# old_line_kick.net
KiCad netlist of a schematic drawn in EAGLE
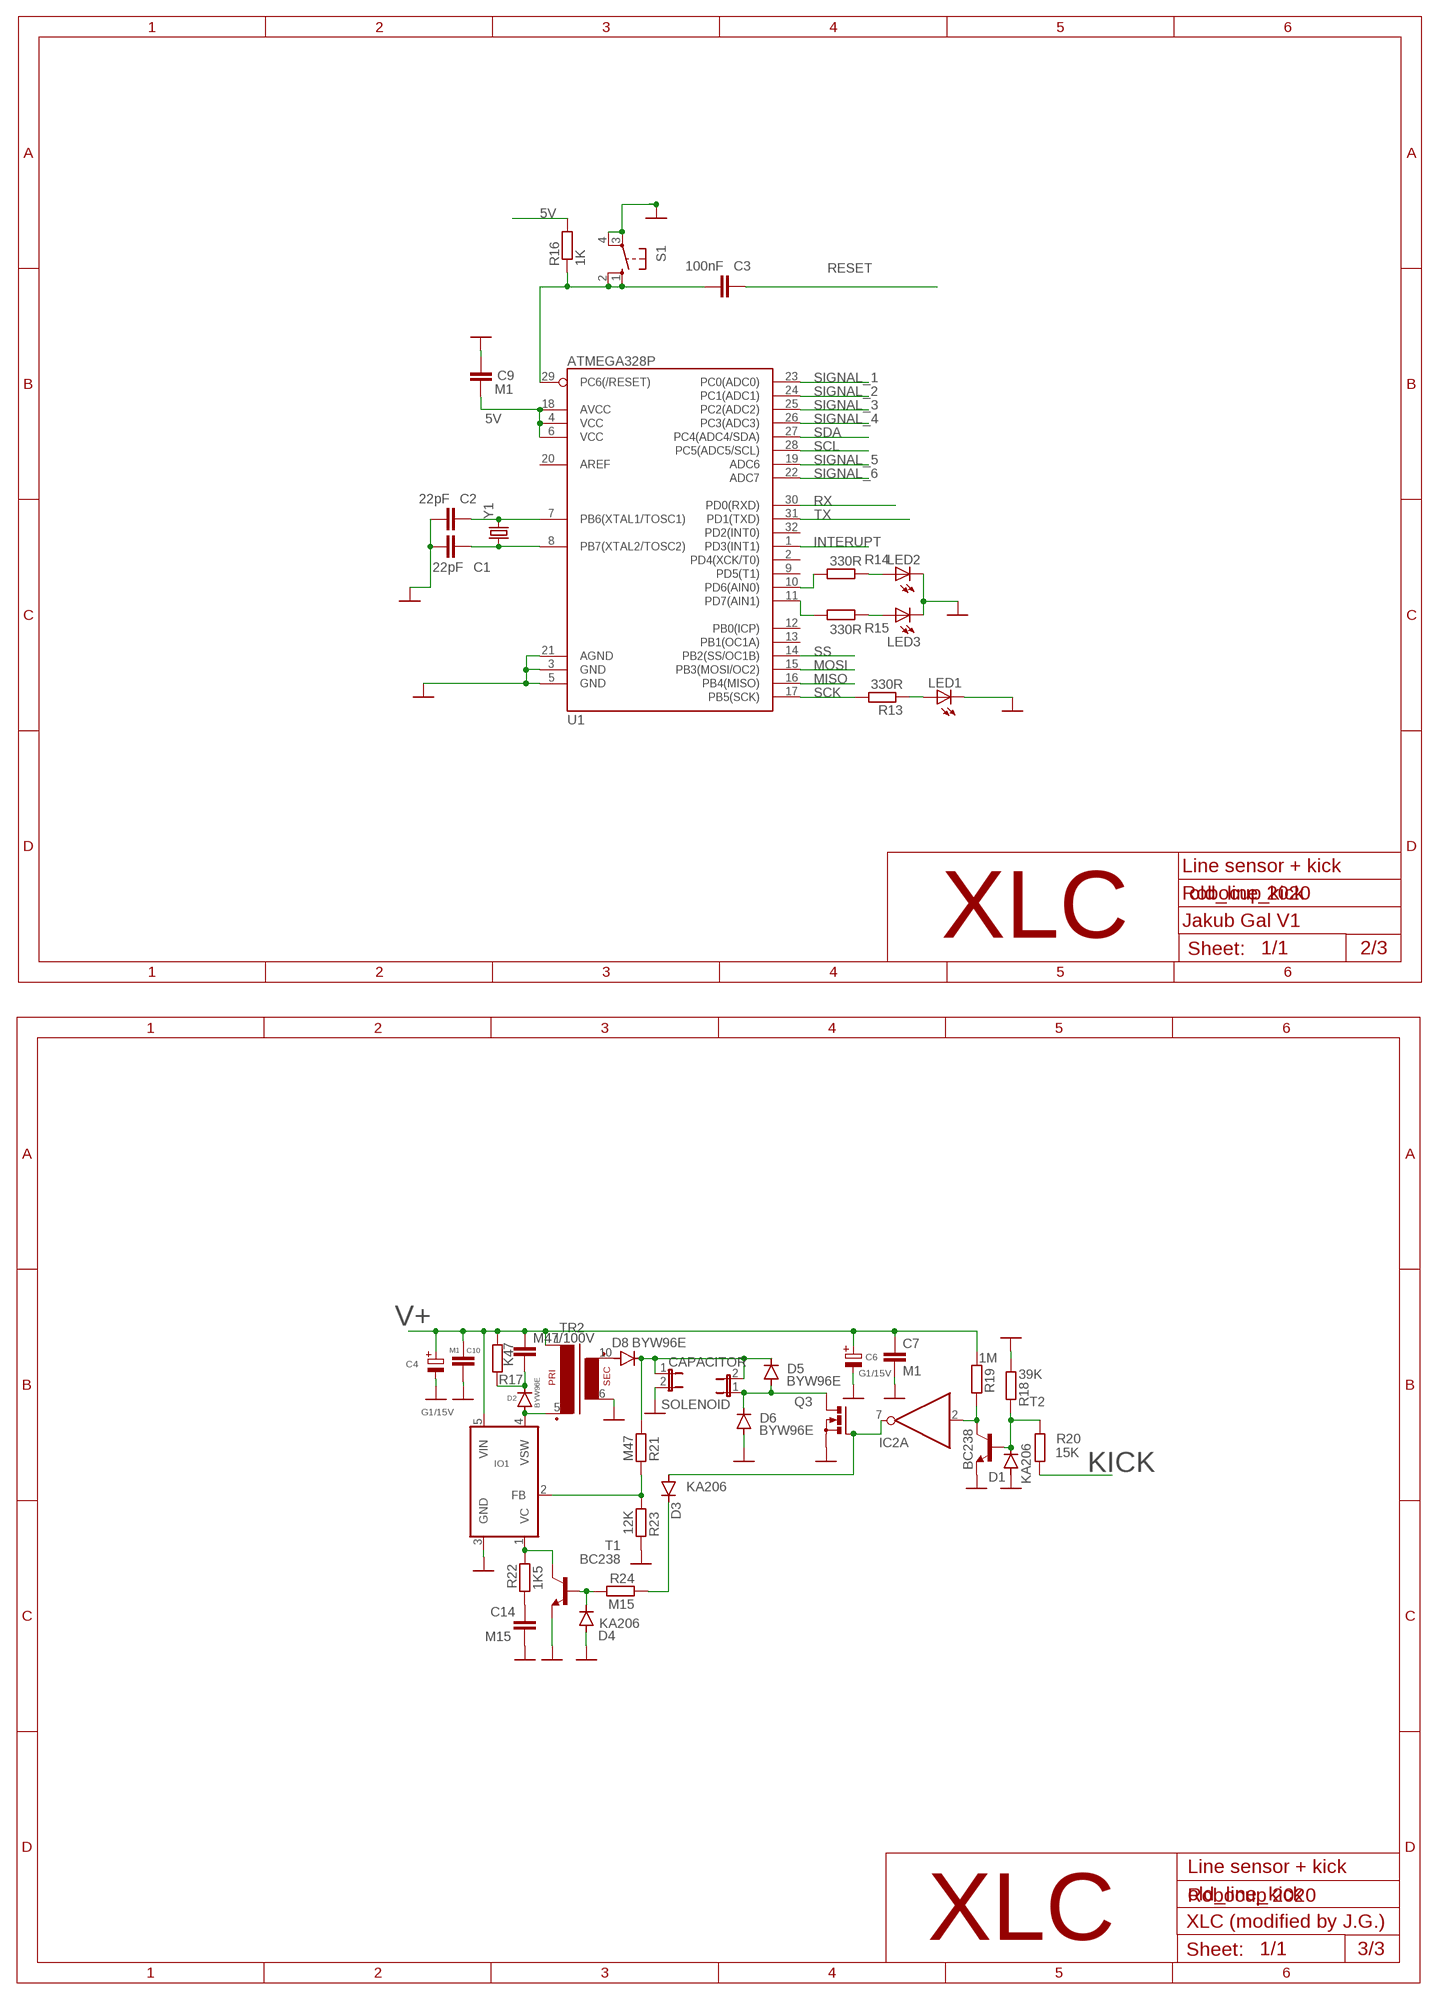
[diagram p0: schematic, sheet 1, part 1 of 2]
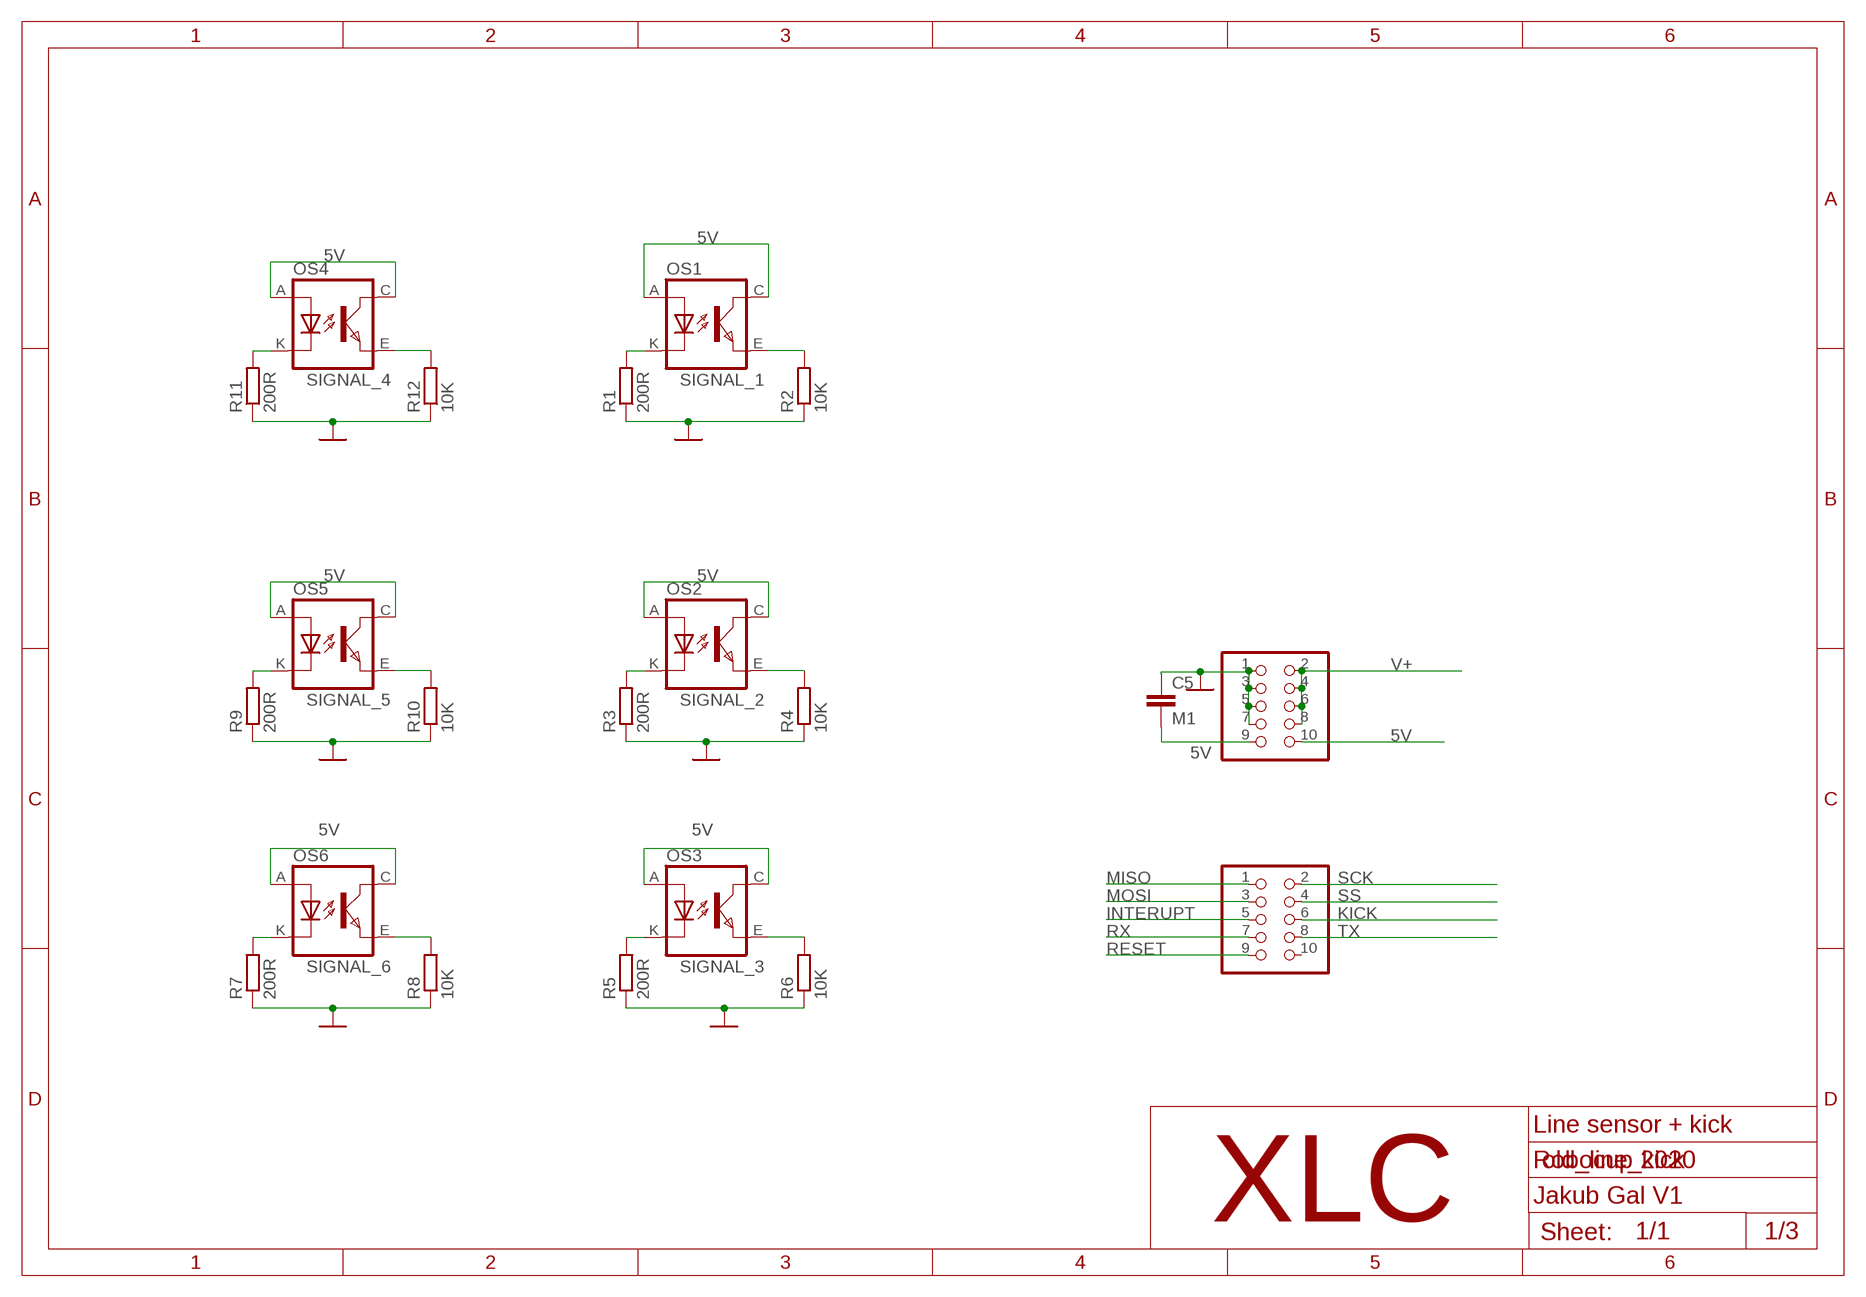
[diagram p1: schematic, sheet 1, part 2 of 2]

(export (version "E")
  (design (tool "Eeschema 10.0.6"))
  (components
    (comp (ref "C1")
      (value "22pF")
      (footprint "eagle-import:C0603")
      (libsource (lib "eagle-import") (part "rcl@1_C-EUC0603"))
    )
    (comp (ref "C2")
      (value "22pF")
      (footprint "eagle-import:C0603")
      (libsource (lib "eagle-import") (part "rcl@1_C-EUC0603"))
    )
    (comp (ref "C3")
      (value "100nF")
      (footprint "eagle-import:C0603")
      (libsource (lib "eagle-import") (part "rcl@1_C-EUC0603"))
    )
    (comp (ref "C4")
      (value "G1/15V")
      (footprint "eagle-import:E-2,5_7-RAD")
      (libsource (lib "eagle-import") (part "KOND-ELEKT-2,5/7"))
    )
    (comp (ref "C5")
      (value "M1")
      (footprint "eagle-import:C0603")
      (libsource (lib "eagle-import") (part "C-EUC0603"))
    )
    (comp (ref "C6")
      (value "G1/15V")
      (footprint "eagle-import:E-2,5_7-RAD")
      (libsource (lib "eagle-import") (part "KOND-ELEKT-2,5/7"))
    )
    (comp (ref "C7")
      (value "M1")
      (footprint "eagle-import:C0805K")
      (libsource (lib "eagle-import") (part "resistor_C-EUC0805K"))
    )
    (comp (ref "C9")
      (value "M1")
      (footprint "eagle-import:C0603")
      (libsource (lib "eagle-import") (part "rcl@1_C-EUC0603"))
    )
    (comp (ref "C10")
      (value "M1")
      (footprint "eagle-import:C0805K")
      (libsource (lib "eagle-import") (part "resistor_C-EUC0805K"))
    )
    (comp (ref "C14")
      (value "M15")
      (footprint "eagle-import:C0805K")
      (libsource (lib "eagle-import") (part "resistor_C-EUC0805K"))
    )
    (comp (ref "CAPACITOR")
      (value "JP1E")
      (footprint "eagle-import:JP1")
      (libsource (lib "eagle-import") (part "JP1E"))
    )
    (comp (ref "D1")
      (value "KA206")
      (footprint "eagle-import:D-7.5")
      (libsource (lib "eagle-import") (part "DIODE-D-7.5"))
    )
    (comp (ref "D2")
      (value "BYW96E")
      (footprint "eagle-import:SOD64-10")
      (libsource (lib "eagle-import") (part "BYW96"))
    )
    (comp (ref "D3")
      (value "KA206")
      (footprint "eagle-import:D-7.5")
      (libsource (lib "eagle-import") (part "DIODE-D-7.5"))
    )
    (comp (ref "D4")
      (value "KA206")
      (footprint "eagle-import:D-7.5")
      (libsource (lib "eagle-import") (part "DIODE-D-7.5"))
    )
    (comp (ref "D5")
      (value "BYW96E")
      (footprint "eagle-import:SOD64-10")
      (libsource (lib "eagle-import") (part "BYW96"))
    )
    (comp (ref "D6")
      (value "BYW96E")
      (footprint "eagle-import:SOD64-10")
      (libsource (lib "eagle-import") (part "BYW96"))
    )
    (comp (ref "D8")
      (value "BYW96E")
      (footprint "eagle-import:SOD64-10")
      (libsource (lib "eagle-import") (part "BYW96"))
    )
    (comp (ref "IC2")
      (value "MIC4423BM")
      (footprint "eagle-import:SO08")
      (libsource (lib "eagle-import") (part "MIC4423BM"))
    )
    (comp (ref "IO1")
      (value "LT1071V")
      (footprint "eagle-import:TO220-5P")
      (libsource (lib "eagle-import") (part "LT1071V"))
    )
    (comp (ref "JP2")
      (value "PINHD-2X5")
      (footprint "eagle-import:2X05")
      (libsource (lib "eagle-import") (part "PINHD-2X5"))
    )
    (comp (ref "JP3")
      (value "PINHD-2X5")
      (footprint "eagle-import:2X05")
      (libsource (lib "eagle-import") (part "PINHD-2X5"))
    )
    (comp (ref "LED1")
      (value "LEDCHIPLED_0603")
      (footprint "eagle-import:CHIPLED_0603")
      (libsource (lib "eagle-import") (part "LEDCHIPLED_0603"))
    )
    (comp (ref "LED2")
      (value "LEDCHIPLED_0603")
      (footprint "eagle-import:CHIPLED_0603")
      (libsource (lib "eagle-import") (part "LEDCHIPLED_0603"))
    )
    (comp (ref "LED3")
      (value "LEDCHIPLED_0603")
      (footprint "eagle-import:CHIPLED_0603")
      (libsource (lib "eagle-import") (part "LEDCHIPLED_0603"))
    )
    (comp (ref "M47/100V")
      (value "C-EUC0805K")
      (footprint "eagle-import:C0805K")
      (libsource (lib "eagle-import") (part "resistor_C-EUC0805K"))
    )
    (comp (ref "OS1")
      (value "TCRT5000")
      (footprint "eagle-import:TCRT5000")
      (libsource (lib "eagle-import") (part "TCRT5000"))
    )
    (comp (ref "OS2")
      (value "TCRT5000")
      (footprint "eagle-import:TCRT5000")
      (libsource (lib "eagle-import") (part "TCRT5000"))
    )
    (comp (ref "OS3")
      (value "TCRT5000")
      (footprint "eagle-import:TCRT5000")
      (libsource (lib "eagle-import") (part "TCRT5000"))
    )
    (comp (ref "OS4")
      (value "TCRT5000")
      (footprint "eagle-import:TCRT5000")
      (fields (field (name "SPICEPREFIX") "O"))
      (libsource (lib "eagle-import") (part "TCRT5000"))
    )
    (comp (ref "OS5")
      (value "TCRT5000")
      (footprint "eagle-import:TCRT5000")
      (libsource (lib "eagle-import") (part "TCRT5000"))
    )
    (comp (ref "OS6")
      (value "TCRT5000")
      (footprint "eagle-import:TCRT5000")
      (fields (field (name "SPICEPREFIX") "O"))
      (libsource (lib "eagle-import") (part "TCRT5000"))
    )
    (comp (ref "Q3")
      (value "PMOSFET_NTO220BV")
      (footprint "eagle-import:TO220BV")
      (libsource (lib "eagle-import") (part "PMOSFET_NTO220BV"))
    )
    (comp (ref "R1")
      (value "200R")
      (footprint "eagle-import:R0603")
      (libsource (lib "eagle-import") (part "R-EU_R0603"))
    )
    (comp (ref "R2")
      (value "10K")
      (footprint "eagle-import:R0603")
      (libsource (lib "eagle-import") (part "R-EU_R0603"))
    )
    (comp (ref "R3")
      (value "200R")
      (footprint "eagle-import:R0603")
      (libsource (lib "eagle-import") (part "R-EU_R0603"))
    )
    (comp (ref "R4")
      (value "10K")
      (footprint "eagle-import:R0603")
      (libsource (lib "eagle-import") (part "R-EU_R0603"))
    )
    (comp (ref "R5")
      (value "200R")
      (footprint "eagle-import:R0603")
      (libsource (lib "eagle-import") (part "R-EU_R0603"))
    )
    (comp (ref "R6")
      (value "10K")
      (footprint "eagle-import:R0603")
      (libsource (lib "eagle-import") (part "R-EU_R0603"))
    )
    (comp (ref "R7")
      (value "200R")
      (footprint "eagle-import:R0603")
      (libsource (lib "eagle-import") (part "R-EU_R0603"))
    )
    (comp (ref "R8")
      (value "10K")
      (footprint "eagle-import:R0603")
      (libsource (lib "eagle-import") (part "R-EU_R0603"))
    )
    (comp (ref "R9")
      (value "200R")
      (footprint "eagle-import:R0603")
      (libsource (lib "eagle-import") (part "R-EU_R0603"))
    )
    (comp (ref "R10")
      (value "10K")
      (footprint "eagle-import:R0603")
      (libsource (lib "eagle-import") (part "R-EU_R0603"))
    )
    (comp (ref "R11")
      (value "200R")
      (footprint "eagle-import:R0603")
      (libsource (lib "eagle-import") (part "R-EU_R0603"))
    )
    (comp (ref "R12")
      (value "10K")
      (footprint "eagle-import:R0603")
      (libsource (lib "eagle-import") (part "R-EU_R0603"))
    )
    (comp (ref "R13")
      (value "330R")
      (footprint "eagle-import:R0603")
      (libsource (lib "eagle-import") (part "R-EU_R0603"))
    )
    (comp (ref "R14")
      (value "330R")
      (footprint "eagle-import:R0603")
      (libsource (lib "eagle-import") (part "R-EU_R0603"))
    )
    (comp (ref "R15")
      (value "330R")
      (footprint "eagle-import:R0603")
      (libsource (lib "eagle-import") (part "R-EU_R0603"))
    )
    (comp (ref "R16")
      (value "1K")
      (footprint "eagle-import:R0603")
      (libsource (lib "eagle-import") (part "R-EU_R0603"))
    )
    (comp (ref "R17")
      (value "K47")
      (footprint "eagle-import:R0603")
      (libsource (lib "eagle-import") (part "resistor_R-EU_R0603"))
    )
    (comp (ref "R18")
      (value "39K")
      (footprint "eagle-import:R0603")
      (libsource (lib "eagle-import") (part "resistor_R-EU_R0603"))
    )
    (comp (ref "R19")
      (value "1M")
      (footprint "eagle-import:R0603")
      (libsource (lib "eagle-import") (part "resistor_R-EU_R0603"))
    )
    (comp (ref "R20")
      (value "15K")
      (footprint "eagle-import:R0603")
      (libsource (lib "eagle-import") (part "resistor_R-EU_R0603"))
    )
    (comp (ref "R21")
      (value "M47")
      (footprint "eagle-import:R0603")
      (libsource (lib "eagle-import") (part "resistor_R-EU_R0603"))
    )
    (comp (ref "R22")
      (value "1K5")
      (footprint "eagle-import:R0603")
      (libsource (lib "eagle-import") (part "resistor_R-EU_R0603"))
    )
    (comp (ref "R23")
      (value "12K")
      (footprint "eagle-import:R0603")
      (libsource (lib "eagle-import") (part "resistor_R-EU_R0603"))
    )
    (comp (ref "R24")
      (value "M15")
      (footprint "eagle-import:R0603")
      (libsource (lib "eagle-import") (part "resistor_R-EU_R0603"))
    )
    (comp (ref "S1")
      (value "10-XX")
      (footprint "eagle-import:B3F-10XX")
      (fields (field (name "MPN") "B3F-1000"))
      (libsource (lib "eagle-import") (part "10-XX"))
    )
    (comp (ref "SOLENOID")
      (value "JP1E")
      (footprint "eagle-import:JP1")
      (libsource (lib "eagle-import") (part "JP1E"))
    )
    (comp (ref "T1")
      (value "BC238")
      (footprint "eagle-import:TO92")
      (libsource (lib "eagle-import") (part "BC238"))
    )
    (comp (ref "T2")
      (value "BC238")
      (footprint "eagle-import:TO92")
      (libsource (lib "eagle-import") (part "BC238"))
    )
    (comp (ref "TR2")
      (value "TRAFO-E10-R\"\"")
      (footprint "eagle-import:TRAFO-EE17X20")
      (libsource (lib "eagle-import") (part "TRAFO-E10-R{dblquote}{dblquote}"))
    )
    (comp (ref "U1")
      (value "ATMEGA328P")
      (footprint "eagle-import:TQFP32-08")
      (libsource (lib "eagle-import") (part "ATMEGA328_SMT"))
    )
    (comp (ref "Y1")
      (value "CRYSTALHC49US")
      (footprint "eagle-import:HC49US")
      (libsource (lib "eagle-import") (part "CRYSTALHC49US"))
    )
  )
  (nets
    (net (code "1") (name "/5V") (class "Default")
      (node (ref "C5") (pin "2") (pinfunction "2_2") (pintype "passive"))
      (node (ref "C9") (pin "1") (pinfunction "1_1") (pintype "passive"))
      (node (ref "JP3") (pin "10") (pinfunction "10_10") (pintype "passive"))
      (node (ref "JP3") (pin "9") (pinfunction "9_9") (pintype "passive"))
      (node (ref "OS1") (pin "A") (pinfunction "ANODE_A") (pintype "passive"))
      (node (ref "OS1") (pin "C") (pinfunction "COLLECTOR_C") (pintype "passive"))
      (node (ref "OS2") (pin "A") (pinfunction "ANODE_A") (pintype "passive"))
      (node (ref "OS2") (pin "C") (pinfunction "COLLECTOR_C") (pintype "passive"))
      (node (ref "OS3") (pin "A") (pinfunction "ANODE_A") (pintype "passive"))
      (node (ref "OS3") (pin "C") (pinfunction "COLLECTOR_C") (pintype "passive"))
      (node (ref "OS4") (pin "A") (pinfunction "ANODE_A") (pintype "passive"))
      (node (ref "OS4") (pin "C") (pinfunction "COLLECTOR_C") (pintype "passive"))
      (node (ref "OS5") (pin "A") (pinfunction "ANODE_A") (pintype "passive"))
      (node (ref "OS5") (pin "C") (pinfunction "COLLECTOR_C") (pintype "passive"))
      (node (ref "OS6") (pin "A") (pinfunction "ANODE_A") (pintype "passive"))
      (node (ref "OS6") (pin "C") (pinfunction "COLLECTOR_C") (pintype "passive"))
      (node (ref "R16") (pin "2") (pinfunction "2_2") (pintype "passive"))
      (node (ref "U1") (pin "18") (pinfunction "AVCC_18") (pintype "bidirectional"))
      (node (ref "U1") (pin "4") (pinfunction "VCC_4") (pintype "bidirectional"))
      (node (ref "U1") (pin "6") (pinfunction "VCC_6") (pintype "bidirectional"))
    )
    (net (code "2") (name "/INTERUPT") (class "Default")
      (node (ref "JP2") (pin "5") (pinfunction "5_5") (pintype "passive"))
      (node (ref "U1") (pin "1") (pinfunction "PD3(INT1)_1") (pintype "bidirectional"))
    )
    (net (code "3") (name "/KICK") (class "Default")
      (node (ref "JP2") (pin "6") (pinfunction "6_6") (pintype "passive"))
      (node (ref "R20") (pin "1") (pinfunction "1_1") (pintype "passive"))
    )
    (net (code "4") (name "/MISO") (class "Default")
      (node (ref "JP2") (pin "1") (pinfunction "1_1") (pintype "passive"))
      (node (ref "U1") (pin "16") (pinfunction "PB4(MISO)_16") (pintype "bidirectional"))
    )
    (net (code "5") (name "/MOSI") (class "Default")
      (node (ref "JP2") (pin "3") (pinfunction "3_3") (pintype "passive"))
      (node (ref "U1") (pin "15") (pinfunction "PB3(MOSI/OC2)_15") (pintype "bidirectional"))
    )
    (net (code "6") (name "/RESET") (class "Default")
      (node (ref "C3") (pin "2") (pinfunction "2_2") (pintype "passive"))
      (node (ref "JP2") (pin "9") (pinfunction "9_9") (pintype "passive"))
    )
    (net (code "7") (name "/RX") (class "Default")
      (node (ref "JP2") (pin "7") (pinfunction "7_7") (pintype "passive"))
      (node (ref "U1") (pin "30") (pinfunction "PD0(RXD)_30") (pintype "bidirectional"))
    )
    (net (code "8") (name "/SCK") (class "Default")
      (node (ref "JP2") (pin "2") (pinfunction "2_2") (pintype "passive"))
      (node (ref "R13") (pin "2") (pinfunction "2_2") (pintype "passive"))
      (node (ref "U1") (pin "17") (pinfunction "PB5(SCK)_17") (pintype "bidirectional"))
    )
    (net (code "9") (name "/SCL") (class "Default")
      (node (ref "U1") (pin "28") (pinfunction "PC5(ADC5/SCL)_28") (pintype "bidirectional"))
    )
    (net (code "10") (name "/SDA") (class "Default")
      (node (ref "U1") (pin "27") (pinfunction "PC4(ADC4/SDA)_27") (pintype "bidirectional"))
    )
    (net (code "11") (name "/SIGNAL_1") (class "Default")
      (node (ref "OS1") (pin "E") (pinfunction "EMITTER_E") (pintype "passive"))
      (node (ref "R2") (pin "2") (pinfunction "2_2") (pintype "passive"))
      (node (ref "U1") (pin "23") (pinfunction "PC0(ADC0)_23") (pintype "bidirectional"))
    )
    (net (code "12") (name "/SIGNAL_2") (class "Default")
      (node (ref "OS2") (pin "E") (pinfunction "EMITTER_E") (pintype "passive"))
      (node (ref "R4") (pin "2") (pinfunction "2_2") (pintype "passive"))
      (node (ref "U1") (pin "24") (pinfunction "PC1(ADC1)_24") (pintype "bidirectional"))
    )
    (net (code "13") (name "/SIGNAL_3") (class "Default")
      (node (ref "OS3") (pin "E") (pinfunction "EMITTER_E") (pintype "passive"))
      (node (ref "R6") (pin "2") (pinfunction "2_2") (pintype "passive"))
      (node (ref "U1") (pin "25") (pinfunction "PC2(ADC2)_25") (pintype "bidirectional"))
    )
    (net (code "14") (name "/SIGNAL_4") (class "Default")
      (node (ref "OS4") (pin "E") (pinfunction "EMITTER_E") (pintype "passive"))
      (node (ref "R12") (pin "2") (pinfunction "2_2") (pintype "passive"))
      (node (ref "U1") (pin "26") (pinfunction "PC3(ADC3)_26") (pintype "bidirectional"))
    )
    (net (code "15") (name "/SIGNAL_5") (class "Default")
      (node (ref "OS5") (pin "E") (pinfunction "EMITTER_E") (pintype "passive"))
      (node (ref "R10") (pin "2") (pinfunction "2_2") (pintype "passive"))
      (node (ref "U1") (pin "19") (pinfunction "ADC6_19") (pintype "bidirectional"))
    )
    (net (code "16") (name "/SIGNAL_6") (class "Default")
      (node (ref "OS6") (pin "E") (pinfunction "EMITTER_E") (pintype "passive"))
      (node (ref "R8") (pin "2") (pinfunction "2_2") (pintype "passive"))
      (node (ref "U1") (pin "22") (pinfunction "ADC7_22") (pintype "bidirectional"))
    )
    (net (code "17") (name "/SS") (class "Default")
      (node (ref "JP2") (pin "4") (pinfunction "4_4") (pintype "passive"))
      (node (ref "U1") (pin "14") (pinfunction "PB2(SS/OC1B)_14") (pintype "bidirectional"))
    )
    (net (code "18") (name "/TX") (class "Default")
      (node (ref "JP2") (pin "8") (pinfunction "8_8") (pintype "passive"))
      (node (ref "U1") (pin "31") (pinfunction "PD1(TXD)_31") (pintype "bidirectional"))
    )
    (net (code "19") (name "/V+") (class "Default")
      (node (ref "C10") (pin "1") (pinfunction "1_1") (pintype "passive"))
      (node (ref "C4") (pin "+") (pinfunction "+_+") (pintype "passive"))
      (node (ref "C6") (pin "+") (pinfunction "+_+") (pintype "passive"))
      (node (ref "C7") (pin "1") (pinfunction "1_1") (pintype "passive"))
      (node (ref "IO1") (pin "5") (pinfunction "VIN_5") (pintype "power_in"))
      (node (ref "JP3") (pin "2") (pinfunction "2_2") (pintype "passive"))
      (node (ref "JP3") (pin "4") (pinfunction "4_4") (pintype "passive"))
      (node (ref "JP3") (pin "6") (pinfunction "6_6") (pintype "passive"))
      (node (ref "JP3") (pin "8") (pinfunction "8_8") (pintype "passive"))
      (node (ref "M47/100V") (pin "1") (pinfunction "1_1") (pintype "passive"))
      (node (ref "R17") (pin "1") (pinfunction "1_1") (pintype "passive"))
      (node (ref "R19") (pin "2") (pinfunction "2_2") (pintype "passive"))
      (node (ref "TR2") (pin "1") (pinfunction "1_1") (pintype "passive"))
    )
    (net (code "20") (name "GND") (class "Default")
      (node (ref "C1") (pin "1") (pinfunction "1_1") (pintype "passive"))
      (node (ref "C10") (pin "2") (pinfunction "2_2") (pintype "passive"))
      (node (ref "C14") (pin "2") (pinfunction "2_2") (pintype "passive"))
      (node (ref "C2") (pin "1") (pinfunction "1_1") (pintype "passive"))
      (node (ref "C4") (pin "-") (pinfunction "-_-") (pintype "passive"))
      (node (ref "C5") (pin "1") (pinfunction "1_1") (pintype "passive"))
      (node (ref "C6") (pin "-") (pinfunction "-_-") (pintype "passive"))
      (node (ref "C7") (pin "2") (pinfunction "2_2") (pintype "passive"))
      (node (ref "C9") (pin "2") (pinfunction "2_2") (pintype "passive"))
      (node (ref "CAPACITOR") (pin "2") (pinfunction "2_2") (pintype "passive"))
      (node (ref "D1") (pin "A") (pinfunction "A_A") (pintype "passive"))
      (node (ref "D4") (pin "A") (pinfunction "A_A") (pintype "passive"))
      (node (ref "D6") (pin "A") (pinfunction "A_A") (pintype "passive"))
      (node (ref "IO1") (pin "3") (pinfunction "GND_3") (pintype "power_in"))
      (node (ref "JP3") (pin "1") (pinfunction "1_1") (pintype "passive"))
      (node (ref "JP3") (pin "3") (pinfunction "3_3") (pintype "passive"))
      (node (ref "JP3") (pin "5") (pinfunction "5_5") (pintype "passive"))
      (node (ref "JP3") (pin "7") (pinfunction "7_7") (pintype "passive"))
      (node (ref "LED1") (pin "C") (pinfunction "C_C") (pintype "passive"))
      (node (ref "LED2") (pin "C") (pinfunction "C_C") (pintype "passive"))
      (node (ref "LED3") (pin "C") (pinfunction "C_C") (pintype "passive"))
      (node (ref "Q3") (pin "S") (pinfunction "S_S") (pintype "passive"))
      (node (ref "R1") (pin "1") (pinfunction "1_1") (pintype "passive"))
      (node (ref "R10") (pin "1") (pinfunction "1_1") (pintype "passive"))
      (node (ref "R11") (pin "1") (pinfunction "1_1") (pintype "passive"))
      (node (ref "R12") (pin "1") (pinfunction "1_1") (pintype "passive"))
      (node (ref "R18") (pin "2") (pinfunction "2_2") (pintype "passive"))
      (node (ref "R2") (pin "1") (pinfunction "1_1") (pintype "passive"))
      (node (ref "R23") (pin "1") (pinfunction "1_1") (pintype "passive"))
      (node (ref "R3") (pin "1") (pinfunction "1_1") (pintype "passive"))
      (node (ref "R4") (pin "1") (pinfunction "1_1") (pintype "passive"))
      (node (ref "R5") (pin "1") (pinfunction "1_1") (pintype "passive"))
      (node (ref "R6") (pin "1") (pinfunction "1_1") (pintype "passive"))
      (node (ref "R7") (pin "1") (pinfunction "1_1") (pintype "passive"))
      (node (ref "R8") (pin "1") (pinfunction "1_1") (pintype "passive"))
      (node (ref "R9") (pin "1") (pinfunction "1_1") (pintype "passive"))
      (node (ref "S1") (pin "3") (pinfunction "P_3") (pintype "passive"))
      (node (ref "S1") (pin "4") (pinfunction "P1_4") (pintype "passive"))
      (node (ref "T1") (pin "1") (pinfunction "E_1") (pintype "passive"))
      (node (ref "T2") (pin "1") (pinfunction "E_1") (pintype "passive"))
      (node (ref "TR2") (pin "6") (pinfunction "3_6") (pintype "passive"))
      (node (ref "U1") (pin "21") (pinfunction "AGND_21") (pintype "bidirectional"))
      (node (ref "U1") (pin "3") (pinfunction "GND_3") (pintype "bidirectional"))
      (node (ref "U1") (pin "5") (pinfunction "GND_5") (pintype "bidirectional"))
    )
    (net (code "21") (name "Net-(C14-Pad1)") (class "Default")
      (node (ref "C14") (pin "1") (pinfunction "1_1") (pintype "passive"))
      (node (ref "R22") (pin "2") (pinfunction "2_2") (pintype "passive"))
    )
    (net (code "22") (name "Net-(CAPACITOR-Pad1)") (class "Default")
      (node (ref "CAPACITOR") (pin "1") (pinfunction "1_1") (pintype "passive"))
      (node (ref "D5") (pin "C") (pinfunction "C_C") (pintype "passive"))
      (node (ref "D8") (pin "C") (pinfunction "C_C") (pintype "passive"))
      (node (ref "R21") (pin "2") (pinfunction "2_2") (pintype "passive"))
      (node (ref "SOLENOID") (pin "2") (pinfunction "2_2") (pintype "passive"))
    )
    (net (code "23") (name "Net-(D2-PadC)") (class "Default")
      (node (ref "D2") (pin "C") (pinfunction "C_C") (pintype "passive"))
      (node (ref "M47/100V") (pin "2") (pinfunction "2_2") (pintype "passive"))
      (node (ref "R17") (pin "2") (pinfunction "2_2") (pintype "passive"))
    )
    (net (code "24") (name "Net-(D3-PadC)") (class "Default")
      (node (ref "D3") (pin "C") (pinfunction "C_C") (pintype "passive"))
      (node (ref "R24") (pin "1") (pinfunction "1_1") (pintype "passive"))
    )
    (net (code "25") (name "Net-(D5-PadA)") (class "Default")
      (node (ref "D5") (pin "A") (pinfunction "A_A") (pintype "passive"))
      (node (ref "D6") (pin "C") (pinfunction "C_C") (pintype "passive"))
      (node (ref "Q3") (pin "D") (pinfunction "D_D") (pintype "passive"))
      (node (ref "SOLENOID") (pin "1") (pinfunction "1_1") (pintype "passive"))
    )
    (net (code "26") (name "Net-(IC2A-IN)") (class "Default")
      (node (ref "IC2") (pin "2") (pinfunction "IN_2") (pintype "input"))
      (node (ref "R19") (pin "1") (pinfunction "1_1") (pintype "passive"))
      (node (ref "T2") (pin "3") (pinfunction "C_3") (pintype "passive"))
    )
    (net (code "27") (name "Net-(IC2A-OUT)") (class "Default")
      (node (ref "D3") (pin "A") (pinfunction "A_A") (pintype "passive"))
      (node (ref "IC2") (pin "7") (pinfunction "OUT_7") (pintype "output"))
      (node (ref "Q3") (pin "G") (pinfunction "G_G") (pintype "passive"))
    )
    (net (code "28") (name "Net-(IO1-FB)") (class "Default")
      (node (ref "IO1") (pin "2") (pinfunction "FB_2") (pintype "input"))
      (node (ref "R21") (pin "1") (pinfunction "1_1") (pintype "passive"))
      (node (ref "R23") (pin "2") (pinfunction "2_2") (pintype "passive"))
    )
    (net (code "29") (name "Net-(IO1-VC)") (class "Default")
      (node (ref "IO1") (pin "1") (pinfunction "VC_1") (pintype "input"))
      (node (ref "R22") (pin "1") (pinfunction "1_1") (pintype "passive"))
      (node (ref "T1") (pin "3") (pinfunction "C_3") (pintype "passive"))
    )
    (net (code "30") (name "Net-(IO1-VSW)") (class "Default")
      (node (ref "D2") (pin "A") (pinfunction "A_A") (pintype "passive"))
      (node (ref "IO1") (pin "4") (pinfunction "VSW_4") (pintype "output"))
      (node (ref "TR2") (pin "5") (pinfunction "2_5") (pintype "passive"))
    )
    (net (code "31") (name "Net-(LED1-PadA)") (class "Default")
      (node (ref "LED1") (pin "A") (pinfunction "A_A") (pintype "passive"))
      (node (ref "R13") (pin "1") (pinfunction "1_1") (pintype "passive"))
    )
    (net (code "32") (name "Net-(LED2-PadA)") (class "Default")
      (node (ref "LED2") (pin "A") (pinfunction "A_A") (pintype "passive"))
      (node (ref "R14") (pin "1") (pinfunction "1_1") (pintype "passive"))
    )
    (net (code "33") (name "Net-(LED3-PadA)") (class "Default")
      (node (ref "LED3") (pin "A") (pinfunction "A_A") (pintype "passive"))
      (node (ref "R15") (pin "1") (pinfunction "1_1") (pintype "passive"))
    )
    (net (code "34") (name "Net-(OS1-CATHODE)") (class "Default")
      (node (ref "OS1") (pin "K") (pinfunction "CATHODE_K") (pintype "passive"))
      (node (ref "R1") (pin "2") (pinfunction "2_2") (pintype "passive"))
    )
    (net (code "35") (name "Net-(OS2-CATHODE)") (class "Default")
      (node (ref "OS2") (pin "K") (pinfunction "CATHODE_K") (pintype "passive"))
      (node (ref "R3") (pin "2") (pinfunction "2_2") (pintype "passive"))
    )
    (net (code "36") (name "Net-(OS3-CATHODE)") (class "Default")
      (node (ref "OS3") (pin "K") (pinfunction "CATHODE_K") (pintype "passive"))
      (node (ref "R5") (pin "2") (pinfunction "2_2") (pintype "passive"))
    )
    (net (code "37") (name "Net-(OS4-CATHODE)") (class "Default")
      (node (ref "OS4") (pin "K") (pinfunction "CATHODE_K") (pintype "passive"))
      (node (ref "R11") (pin "2") (pinfunction "2_2") (pintype "passive"))
    )
    (net (code "38") (name "Net-(OS5-CATHODE)") (class "Default")
      (node (ref "OS5") (pin "K") (pinfunction "CATHODE_K") (pintype "passive"))
      (node (ref "R9") (pin "2") (pinfunction "2_2") (pintype "passive"))
    )
    (net (code "39") (name "Net-(OS6-CATHODE)") (class "Default")
      (node (ref "OS6") (pin "K") (pinfunction "CATHODE_K") (pintype "passive"))
      (node (ref "R7") (pin "2") (pinfunction "2_2") (pintype "passive"))
    )
    (net (code "40") (name "Net-(S1-S)") (class "Default")
      (node (ref "C3") (pin "1") (pinfunction "1_1") (pintype "passive"))
      (node (ref "R16") (pin "1") (pinfunction "1_1") (pintype "passive"))
      (node (ref "S1") (pin "1") (pinfunction "S_1") (pintype "passive"))
      (node (ref "S1") (pin "2") (pinfunction "S1_2") (pintype "passive"))
      (node (ref "U1") (pin "29") (pinfunction "PC6(/RESET)_29") (pintype "bidirectional"))
    )
    (net (code "41") (name "Net-(T1-B)") (class "Default")
      (node (ref "D4") (pin "C") (pinfunction "C_C") (pintype "passive"))
      (node (ref "R24") (pin "2") (pinfunction "2_2") (pintype "passive"))
      (node (ref "T1") (pin "2") (pinfunction "B_2") (pintype "passive"))
    )
    (net (code "42") (name "Net-(T2-B)") (class "Default")
      (node (ref "D1") (pin "C") (pinfunction "C_C") (pintype "passive"))
      (node (ref "R18") (pin "1") (pinfunction "1_1") (pintype "passive"))
      (node (ref "R20") (pin "2") (pinfunction "2_2") (pintype "passive"))
      (node (ref "T2") (pin "2") (pinfunction "B_2") (pintype "passive"))
    )
    (net (code "43") (name "Net-(TR2-4)") (class "Default")
      (node (ref "D8") (pin "A") (pinfunction "A_A") (pintype "passive"))
      (node (ref "TR2") (pin "10") (pinfunction "4_10") (pintype "passive"))
    )
    (net (code "44") (name "Net-(U1-PB6(XTAL1{slash}TOSC1))") (class "Default")
      (node (ref "C2") (pin "2") (pinfunction "2_2") (pintype "passive"))
      (node (ref "U1") (pin "7") (pinfunction "PB6(XTAL1/TOSC1)_7") (pintype "bidirectional"))
      (node (ref "Y1") (pin "2") (pinfunction "2_2") (pintype "passive"))
    )
    (net (code "45") (name "Net-(U1-PB7(XTAL2{slash}TOSC2))") (class "Default")
      (node (ref "C1") (pin "2") (pinfunction "2_2") (pintype "passive"))
      (node (ref "U1") (pin "8") (pinfunction "PB7(XTAL2/TOSC2)_8") (pintype "bidirectional"))
      (node (ref "Y1") (pin "1") (pinfunction "1_1") (pintype "passive"))
    )
    (net (code "46") (name "Net-(U1-PD6(AIN0))") (class "Default")
      (node (ref "R14") (pin "2") (pinfunction "2_2") (pintype "passive"))
      (node (ref "U1") (pin "10") (pinfunction "PD6(AIN0)_10") (pintype "bidirectional"))
    )
    (net (code "47") (name "Net-(U1-PD7(AIN1))") (class "Default")
      (node (ref "R15") (pin "2") (pinfunction "2_2") (pintype "passive"))
      (node (ref "U1") (pin "11") (pinfunction "PD7(AIN1)_11") (pintype "bidirectional"))
    )
    (net (code "48") (name "unconnected-(JP2-Pad10)") (class "Default")
      (node (ref "JP2") (pin "10") (pinfunction "10_10") (pintype "passive"))
    )
    (net (code "49") (name "unconnected-(U1-AREF-Pad20)") (class "Default")
      (node (ref "U1") (pin "20") (pinfunction "AREF_20") (pintype "bidirectional"))
    )
    (net (code "50") (name "unconnected-(U1-PB0(ICP)-Pad12)") (class "Default")
      (node (ref "U1") (pin "12") (pinfunction "PB0(ICP)_12") (pintype "bidirectional"))
    )
    (net (code "51") (name "unconnected-(U1-PB1(OC1A)-Pad13)") (class "Default")
      (node (ref "U1") (pin "13") (pinfunction "PB1(OC1A)_13") (pintype "bidirectional"))
    )
    (net (code "52") (name "unconnected-(U1-PD2(INT0)-Pad32)") (class "Default")
      (node (ref "U1") (pin "32") (pinfunction "PD2(INT0)_32") (pintype "bidirectional"))
    )
    (net (code "53") (name "unconnected-(U1-PD4(XCK{slash}T0)-Pad2)") (class "Default")
      (node (ref "U1") (pin "2") (pinfunction "PD4(XCK/T0)_2") (pintype "bidirectional"))
    )
    (net (code "54") (name "unconnected-(U1-PD5(T1)-Pad9)") (class "Default")
      (node (ref "U1") (pin "9") (pinfunction "PD5(T1)_9") (pintype "bidirectional"))
    )
  )
)
